# Synchronizer.net
KiCad netlist of a schematic drawn in Altium Designer
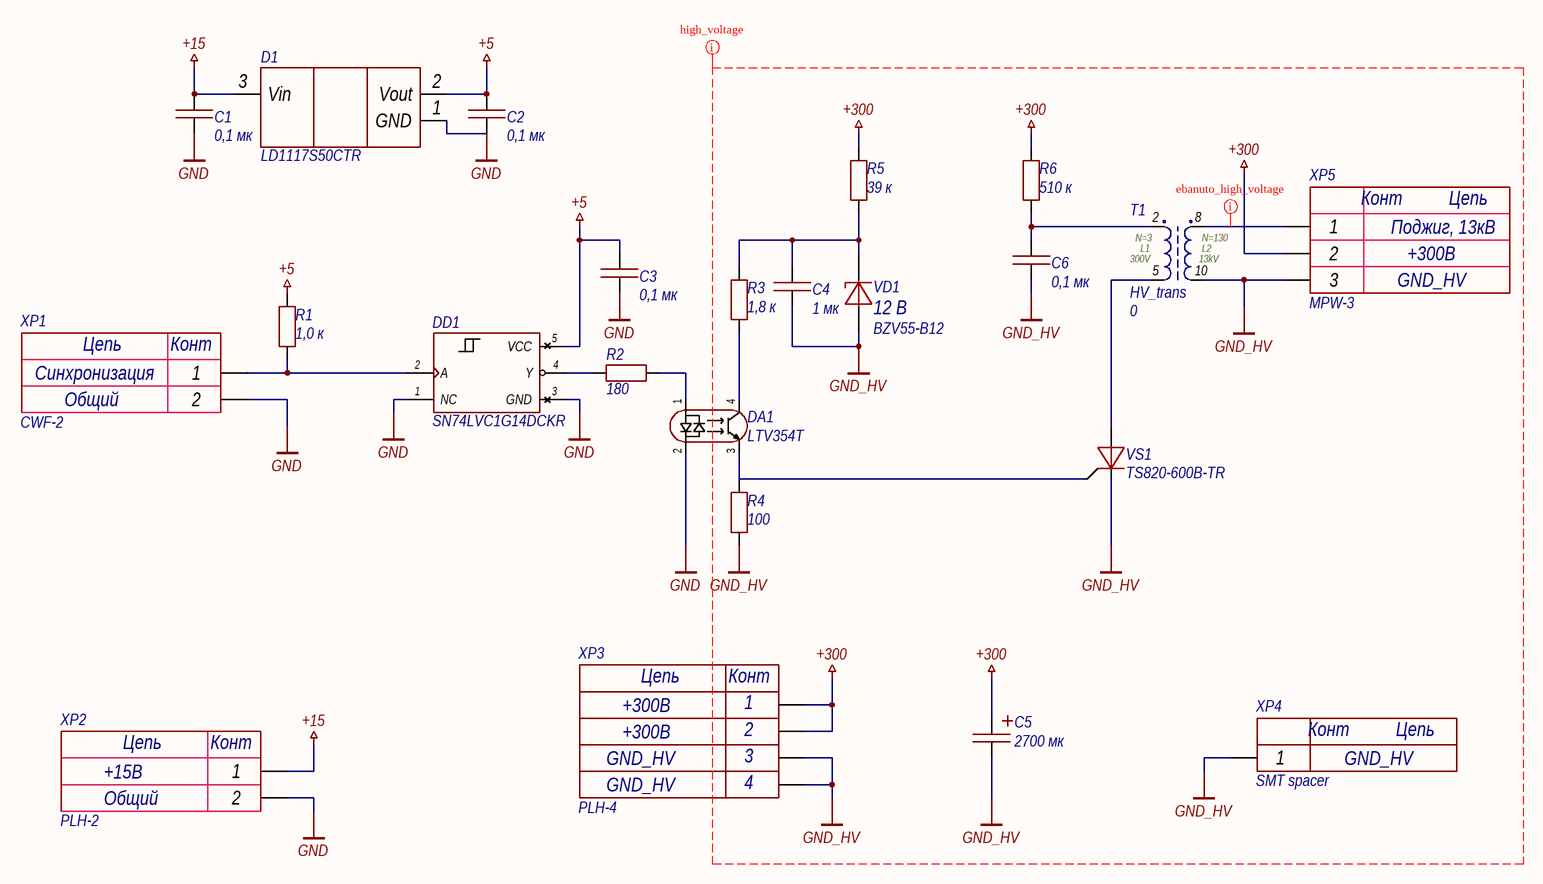
[diagram p0: Synchronizer.SchDoc]

(export (version "E")
  (design (tool "Eeschema 10.0.6"))
  (components
    (comp (ref "C1")
      (value "0,1 мк")
      (footprint "0603C")
      (description "Конденсатор")
      (fields (field (name "PART NUMBER") "Capacitor_0,1u_10_50V_X7R_0603C") (field (name "TOLERANCE") "0,1"))
      (libsource (lib "Hydrolib") (part "Capacitor"))
    )
    (comp (ref "C2")
      (value "0,1 мк")
      (footprint "0603C")
      (description "Конденсатор")
      (fields (field (name "PART NUMBER") "Capacitor_0,1u_10_50V_X7R_0603C") (field (name "TOLERANCE") "0,1"))
      (libsource (lib "Hydrolib") (part "Capacitor"))
    )
    (comp (ref "C3")
      (value "0,1 мк")
      (footprint "0603C")
      (description "Конденсатор")
      (fields (field (name "PART NUMBER") "Capacitor_0,1u_10_50V_X7R_0603C") (field (name "TOLERANCE") "0,1"))
      (libsource (lib "Hydrolib") (part "Capacitor"))
    )
    (comp (ref "C4")
      (value "1 мк")
      (footprint "0603C")
      (description "Конденсатор")
      (fields (field (name "PART NUMBER") "Capacitor_1u_10_50V_X7R_0603C") (field (name "TOLERANCE") "0,1"))
      (libsource (lib "Hydrolib") (part "Capacitor"))
    )
    (comp (ref "C5")
      (value "2700 мк")
      (footprint "42x103_radial")
      (description "Конденсатор алюминиевый электролитический 2700мкФ 400В 20%")
      (fields (field (name "PART NUMBER") "JCCON 2700uF 400V") (field (name "TOLERANCE") "20"))
      (libsource (lib "Hydrolib") (part "Capacitor_polar"))
    )
    (comp (ref "C6")
      (value "0,1 мк")
      (footprint "1812C")
      (description "Конденсатор")
      (fields
        (field (name "PART NUMBER") "Capacitor_0,1u_10_1000V_X7R_1812C")
        (field (name "TOLERANCE") "0,1")
      )
      (libsource (lib "Hydrolib") (part "Capacitor"))
    )
    (comp (ref "D1")
      (value "LD1117S50CTR")
      (footprint "SOT223")
      (description "Линейный стабилизатор напряжения")
      (libsource (lib "Hydrolib") (part "LD1117S50CTR"))
    )
    (comp (ref "DA1")
      (value "LTV354T")
      (footprint "SOP4-2_54")
      (description "Оптопара с транзисторным выходом, UMW")
      (libsource (lib "Hydrolib") (part "LTV354"))
    )
    (comp (ref "DD1")
      (value "SN74LVC1G14DCKR")
      (footprint "SC-70-5")
      (description "Одноканальный инвертор с триггером Шмитта")
      (libsource (lib "Hydrolib") (part "SN74LVC1G14DCKR"))
    )
    (comp (ref "R1")
      (value "1,0 к")
      (footprint "0603R")
      (description "Резистор номиналом 1,0 кОм и точностью 1%")
      (fields (field (name "PART NUMBER") "Resistor_1.0k_1_0603") (field (name "TOLERANCE") "1%"))
      (libsource (lib "Hydrolib") (part "Resistor"))
    )
    (comp (ref "R2")
      (value "180")
      (footprint "0603R")
      (description "Резистор номиналом 180 Ом и точностью 1%")
      (fields (field (name "PART NUMBER") "Resistor_180_1_0603") (field (name "TOLERANCE") "1%"))
      (libsource (lib "") (part "Resistor_1"))
    )
    (comp (ref "R3")
      (value "1,8 к")
      (footprint "0603R")
      (description "Резистор номиналом 1,8 кОм и точностью 1%")
      (fields (field (name "PART NUMBER") "Resistor_1.8k_1_0603") (field (name "TOLERANCE") "1%"))
      (libsource (lib "Hydrolib") (part "Resistor"))
    )
    (comp (ref "R4")
      (value "100")
      (footprint "0603R")
      (description "Резистор номиналом 100 Ом и точностью 1%")
      (fields (field (name "PART NUMBER") "Resistor_100_1_0603") (field (name "TOLERANCE") "1%"))
      (libsource (lib "Hydrolib") (part "Resistor"))
    )
    (comp (ref "R5")
      (value "39 к")
      (footprint "0603R")
      (description "Резистор номиналом 39 кОм и точностью 1%")
      (fields (field (name "PART NUMBER") "Resistor_39k_1_0603") (field (name "TOLERANCE") "1%"))
      (libsource (lib "Hydrolib") (part "Resistor"))
    )
    (comp (ref "R6")
      (value "510 к")
      (footprint "0603R")
      (description "Резистор номиналом 510 кОм и точностью 1%")
      (fields (field (name "PART NUMBER") "Resistor_510k_1_0603") (field (name "TOLERANCE") "1%"))
      (libsource (lib "Hydrolib") (part "Resistor"))
    )
    (comp (ref "T1")
      (value "HV_trans")
      (footprint "EE16_transformer")
      (description "Импульсный трансформатор для поджига вспышки")
      (fields (field (name "ALTIUM_VALUE") "0"))
      (libsource (lib "Hydrolib") (part "HV_trans"))
    )
    (comp (ref "VD1")
      (value "BZV55-B12")
      (footprint "mini_MELF_3.5mm")
      (description "Стабилитрон 12В, 5%, 0.5Вт")
      (fields (field (name "ALTIUM_VALUE") "12 В"))
      (libsource (lib "Hydrolib") (part "Zener"))
    )
    (comp (ref "VS1")
      (value "TS820-600B-TR")
      (footprint "DPAK")
      (description "Тиристор 600В 8А")
      (libsource (lib "Hydrolib") (part "thyristor"))
    )
    (comp (ref "XP1")
      (value "CWF-2")
      (footprint "CWF-2")
      (description "2-пиновый разъем с ключом")
      (fields (field (name "VALUE2") "Общий") (field (name "VALUE1") "Синхронизация"))
      (libsource (lib "Hydrolib") (part "Conn_2pin"))
    )
    (comp (ref "XP2")
      (value "PLH-2")
      (footprint "PLH2_type18")
      (description "Гребенка высокая 2 пина типоразмер 18 (промежуток 10.4мм) Connfly")
      (fields (field (name "VALUE2") "Общий") (field (name "VALUE1") "+15В"))
      (libsource (lib "Hydrolib") (part "Conn_2pin"))
    )
    (comp (ref "XP3")
      (value "PLH-4")
      (footprint "PLH4_type18")
      (description "Гребенка высокая 4 пина типоразмер 18 (промежуток 10.4мм) Connfly")
      (fields
        (field (name "VALUE3") "GND_HV")
        (field (name "VALUE2") "+300В")
        (field (name "VALUE4") "GND_HV")
        (field (name "VALUE1") "+300В")
      )
      (libsource (lib "Hydrolib") (part "Conn_4pin"))
    )
    (comp (ref "XP4")
      (value "SMT spacer")
      (footprint "9774030151")
      (fields (field (name "VALUE1") "GND_HV") (field (name "PART NUMBER") "SMT_spacer_nut"))
      (libsource (lib "Hydrolib") (part "Conn_1pin"))
    )
    (comp (ref "XP5")
      (value "MPW-3")
      (footprint "MPW-3")
      (description "MPW-3 , Вилка на плату 5.08мм прямая 3pin")
      (fields
        (field (name "VALUE3") "GND_HV")
        (field (name "VALUE2") "+300В")
        (field (name "VALUE1") "Поджиг, 13кВ")
      )
      (libsource (lib "Hydrolib") (part "Conn_3pin"))
    )
  )
  (nets
    (net (code "1") (name "+5") (class "Default")
      (node (ref "C2") (pin "2") (pinfunction "2_2") (pintype "passive"))
      (node (ref "C3") (pin "2") (pinfunction "2_2") (pintype "passive"))
      (node (ref "D1") (pin "2") (pinfunction "Vout_2") (pintype "passive"))
      (node (ref "DD1") (pin "5") (pinfunction "VCC_5") (pintype "power_in"))
      (node (ref "R1") (pin "2") (pinfunction "2_2") (pintype "passive"))
    )
    (net (code "2") (name "+15") (class "Default")
      (node (ref "C1") (pin "2") (pinfunction "2_2") (pintype "passive"))
      (node (ref "D1") (pin "3") (pinfunction "Vin_3") (pintype "passive"))
      (node (ref "XP2") (pin "1") (pinfunction "1_1") (pintype "passive"))
    )
    (net (code "3") (name "+300") (class "Default")
      (node (ref "C5") (pin "1") (pinfunction "1_1") (pintype "passive"))
      (node (ref "R5") (pin "2") (pinfunction "2_2") (pintype "passive"))
      (node (ref "R6") (pin "2") (pinfunction "2_2") (pintype "passive"))
      (node (ref "XP3") (pin "1") (pinfunction "1_1") (pintype "passive"))
      (node (ref "XP3") (pin "2") (pinfunction "2_2") (pintype "passive"))
      (node (ref "XP5") (pin "2") (pinfunction "2_2") (pintype "passive"))
    )
    (net (code "4") (name "GND") (class "Default")
      (node (ref "C1") (pin "1") (pinfunction "1_1") (pintype "passive"))
      (node (ref "C2") (pin "1") (pinfunction "1_1") (pintype "passive"))
      (node (ref "C3") (pin "1") (pinfunction "1_1") (pintype "passive"))
      (node (ref "D1") (pin "1") (pinfunction "GND_1") (pintype "passive"))
      (node (ref "DA1") (pin "2") (pinfunction "C_2") (pintype "passive"))
      (node (ref "DD1") (pin "1") (pinfunction "NC_1") (pintype "passive"))
      (node (ref "DD1") (pin "3") (pinfunction "GND_3") (pintype "power_in"))
      (node (ref "XP1") (pin "2") (pinfunction "2_2") (pintype "passive"))
      (node (ref "XP2") (pin "2") (pinfunction "2_2") (pintype "passive"))
    )
    (net (code "5") (name "GND_HV") (class "Default")
      (node (ref "C4") (pin "1") (pinfunction "1_1") (pintype "passive"))
      (node (ref "C5") (pin "2") (pinfunction "2_2") (pintype "passive"))
      (node (ref "C6") (pin "1") (pinfunction "1_1") (pintype "passive"))
      (node (ref "R4") (pin "1") (pinfunction "1_1") (pintype "passive"))
      (node (ref "T1") (pin "10") (pinfunction "10_10") (pintype "passive"))
      (node (ref "VD1") (pin "1") (pinfunction "1_1") (pintype "passive"))
      (node (ref "VS1") (pin "1") (pinfunction "1_1") (pintype "passive"))
      (node (ref "XP3") (pin "3") (pinfunction "3_3") (pintype "passive"))
      (node (ref "XP3") (pin "4") (pinfunction "4_4") (pintype "passive"))
      (node (ref "XP4") (pin "1") (pinfunction "1_1") (pintype "passive"))
      (node (ref "XP5") (pin "3") (pinfunction "3_3") (pintype "passive"))
    )
    (net (code "6") (name "Net-(C4-Pad2)") (class "Default")
      (node (ref "C4") (pin "2") (pinfunction "2_2") (pintype "passive"))
      (node (ref "R3") (pin "2") (pinfunction "2_2") (pintype "passive"))
      (node (ref "R5") (pin "1") (pinfunction "1_1") (pintype "passive"))
      (node (ref "VD1") (pin "2") (pinfunction "2_2") (pintype "passive"))
    )
    (net (code "7") (name "Net-(C6-Pad2)") (class "Default")
      (node (ref "C6") (pin "2") (pinfunction "2_2") (pintype "passive"))
      (node (ref "R6") (pin "1") (pinfunction "1_1") (pintype "passive"))
      (node (ref "T1") (pin "2") (pinfunction "2_2") (pintype "passive"))
    )
    (net (code "8") (name "Net-(DA1-A)") (class "Default")
      (node (ref "DA1") (pin "1") (pinfunction "A_1") (pintype "passive"))
      (node (ref "R2") (pin "2") (pinfunction "2_2") (pintype "passive"))
    )
    (net (code "9") (name "Net-(DA1-CT)") (class "Default")
      (node (ref "DA1") (pin "4") (pinfunction "CT_4") (pintype "passive"))
      (node (ref "R3") (pin "1") (pinfunction "1_1") (pintype "passive"))
    )
    (net (code "10") (name "Net-(DA1-ET)") (class "Default")
      (node (ref "DA1") (pin "3") (pinfunction "ET_3") (pintype "passive"))
      (node (ref "R4") (pin "2") (pinfunction "2_2") (pintype "passive"))
      (node (ref "VS1") (pin "3") (pinfunction "3_3") (pintype "passive"))
    )
    (net (code "11") (name "Net-(DD1-A)") (class "Default")
      (node (ref "DD1") (pin "2") (pinfunction "A_2") (pintype "passive"))
      (node (ref "R1") (pin "1") (pinfunction "1_1") (pintype "passive"))
      (node (ref "XP1") (pin "1") (pinfunction "1_1") (pintype "passive"))
    )
    (net (code "12") (name "Net-(DD1-Y)") (class "Default")
      (node (ref "DD1") (pin "4") (pinfunction "Y_4") (pintype "passive"))
      (node (ref "R2") (pin "1") (pinfunction "1_1") (pintype "passive"))
    )
    (net (code "13") (name "Net-(T1-Pad5)") (class "Default")
      (node (ref "T1") (pin "5") (pinfunction "5_5") (pintype "passive"))
      (node (ref "VS1") (pin "2") (pinfunction "2_2") (pintype "passive"))
    )
    (net (code "14") (name "Net-(T1-Pad8)") (class "Default")
      (node (ref "T1") (pin "8") (pinfunction "8_8") (pintype "passive"))
      (node (ref "XP5") (pin "1") (pinfunction "1_1") (pintype "passive"))
    )
  )
)
